# Output.net
KiCad netlist of a schematic drawn in EAGLE
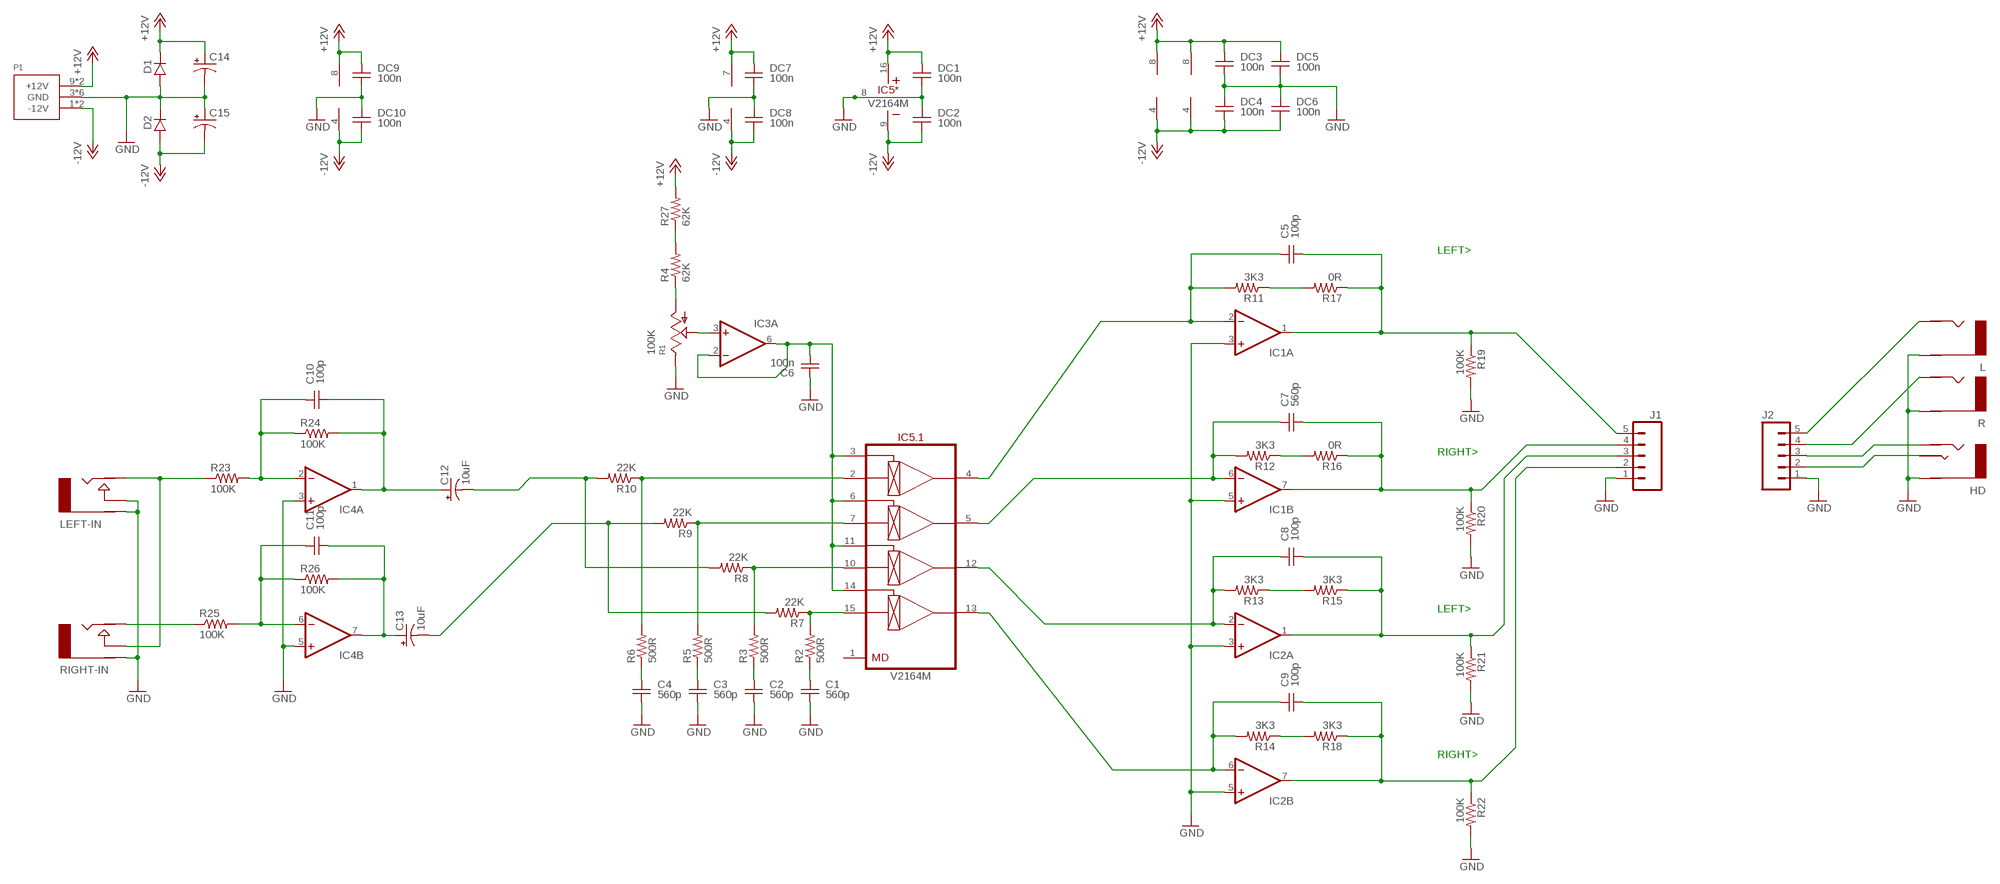
[diagram p0: schematic, sheet 1]

(export (version "E")
  (design (tool "Eeschema 10.0.6"))
  (components
    (comp (ref "C1")
      (value "560p")
      (footprint "eagle-import:C-0805")
      (libsource (lib "eagle-import") (part "CAPACITOR0805"))
    )
    (comp (ref "C2")
      (value "560p")
      (footprint "eagle-import:C-0805")
      (libsource (lib "eagle-import") (part "CAPACITOR0805"))
    )
    (comp (ref "C3")
      (value "560p")
      (footprint "eagle-import:C-0805")
      (libsource (lib "eagle-import") (part "CAPACITOR0805"))
    )
    (comp (ref "C4")
      (value "560p")
      (footprint "eagle-import:C-0805")
      (libsource (lib "eagle-import") (part "CAPACITOR0805"))
    )
    (comp (ref "C5")
      (value "100p")
      (footprint "eagle-import:C-0805")
      (libsource (lib "eagle-import") (part "CAPACITOR0805"))
    )
    (comp (ref "C6")
      (value "100n")
      (footprint "eagle-import:C-0805")
      (libsource (lib "eagle-import") (part "CAPACITOR0805"))
    )
    (comp (ref "C7")
      (value "560p")
      (footprint "eagle-import:C-0805")
      (libsource (lib "eagle-import") (part "CAPACITOR0805"))
    )
    (comp (ref "C8")
      (value "100p")
      (footprint "eagle-import:C-0805")
      (libsource (lib "eagle-import") (part "CAPACITOR0805"))
    )
    (comp (ref "C9")
      (value "100p")
      (footprint "eagle-import:C-0805")
      (libsource (lib "eagle-import") (part "CAPACITOR0805"))
    )
    (comp (ref "C10")
      (value "100p")
      (footprint "eagle-import:C-0805")
      (libsource (lib "eagle-import") (part "CAPACITOR0805"))
    )
    (comp (ref "C11")
      (value "100p")
      (footprint "eagle-import:C-0805")
      (libsource (lib "eagle-import") (part "CAPACITOR0805"))
    )
    (comp (ref "C12")
      (value "10uF")
      (footprint "eagle-import:PANASONIC_C")
      (libsource (lib "eagle-import") (part "SparkFun-Passives_CAP_POLC"))
    )
    (comp (ref "C13")
      (value "10uF")
      (footprint "eagle-import:PANASONIC_C")
      (libsource (lib "eagle-import") (part "SparkFun-Passives_CAP_POLC"))
    )
    (comp (ref "C14")
      (value "CAP_POLPTH2")
      (footprint "eagle-import:CPOL-RADIAL-10UF-25V")
      (libsource (lib "eagle-import") (part "CAP_POLPTH2"))
    )
    (comp (ref "C15")
      (value "CAP_POLPTH2")
      (footprint "eagle-import:CPOL-RADIAL-10UF-25V")
      (libsource (lib "eagle-import") (part "CAP_POLPTH2"))
    )
    (comp (ref "D1")
      (value "DIODESMA")
      (footprint "eagle-import:SMA")
      (libsource (lib "eagle-import") (part "DIODESMA"))
    )
    (comp (ref "D2")
      (value "DIODESMA")
      (footprint "eagle-import:SMA")
      (libsource (lib "eagle-import") (part "DIODESMA"))
    )
    (comp (ref "DC1")
      (value "100n")
      (footprint "eagle-import:C-0805")
      (libsource (lib "eagle-import") (part "CAPACITOR0805"))
    )
    (comp (ref "DC2")
      (value "100n")
      (footprint "eagle-import:C-0805")
      (libsource (lib "eagle-import") (part "CAPACITOR0805"))
    )
    (comp (ref "DC3")
      (value "100n")
      (footprint "eagle-import:C-0805")
      (libsource (lib "eagle-import") (part "CAPACITOR0805"))
    )
    (comp (ref "DC4")
      (value "100n")
      (footprint "eagle-import:C-0805")
      (libsource (lib "eagle-import") (part "CAPACITOR0805"))
    )
    (comp (ref "DC5")
      (value "100n")
      (footprint "eagle-import:C-0805")
      (libsource (lib "eagle-import") (part "CAPACITOR0805"))
    )
    (comp (ref "DC6")
      (value "100n")
      (footprint "eagle-import:C-0805")
      (libsource (lib "eagle-import") (part "CAPACITOR0805"))
    )
    (comp (ref "DC7")
      (value "100n")
      (footprint "eagle-import:C-0805")
      (libsource (lib "eagle-import") (part "CAPACITOR0805"))
    )
    (comp (ref "DC8")
      (value "100n")
      (footprint "eagle-import:C-0805")
      (libsource (lib "eagle-import") (part "CAPACITOR0805"))
    )
    (comp (ref "DC9")
      (value "100n")
      (footprint "eagle-import:C-0805")
      (libsource (lib "eagle-import") (part "CAPACITOR0805"))
    )
    (comp (ref "DC10")
      (value "100n")
      (footprint "eagle-import:C-0805")
      (libsource (lib "eagle-import") (part "CAPACITOR0805"))
    )
    (comp (ref "HD")
      (value "AUDIO-JACK_STEREO")
      (footprint "eagle-import:NJ3FD")
      (libsource (lib "eagle-import") (part "AUDIO-JACK_STEREO"))
    )
    (comp (ref "IC1")
      (value "OPAMP-DUAL")
      (footprint "eagle-import:SO08")
      (libsource (lib "eagle-import") (part "OPAMP-DUAL"))
    )
    (comp (ref "IC2")
      (value "OPAMP-DUAL")
      (footprint "eagle-import:SO08")
      (libsource (lib "eagle-import") (part "OPAMP-DUAL"))
    )
    (comp (ref "IC3")
      (value "OPAMP-SINGLE")
      (footprint "eagle-import:SO08")
      (libsource (lib "eagle-import") (part "OPAMP-SINGLE"))
    )
    (comp (ref "IC4")
      (value "OPAMP-DUAL")
      (footprint "eagle-import:SO08")
      (libsource (lib "eagle-import") (part "OPAMP-DUAL"))
    )
    (comp (ref "IC5")
      (value "V2164M")
      (footprint "eagle-import:SO-16")
      (libsource (lib "eagle-import") (part "V2164M"))
    )
    (comp (ref "J1")
      (value "CONN2")
      (footprint "eagle-import:1X05_LOCK")
      (libsource (lib "eagle-import") (part "M05LOCK"))
    )
    (comp (ref "J2")
      (value "CONN")
      (footprint "eagle-import:1X05_LOCK")
      (libsource (lib "eagle-import") (part "M05LOCK"))
    )
    (comp (ref "L")
      (value "AUDIO-JACK-MONO")
      (footprint "eagle-import:NJ2FD")
      (libsource (lib "eagle-import") (part "AUDIO-JACK-MONO"))
    )
    (comp (ref "LEFT-IN")
      (value "AUDIO-JACKINLINE")
      (footprint "eagle-import:ERTHENVAR-JACK-INLINE")
      (libsource (lib "eagle-import") (part "AUDIO-JACKINLINE"))
    )
    (comp (ref "P1")
      (value "POWER_SIMPLE10_SHROUDED")
      (footprint "eagle-import:POWER_10_SHROUDED")
      (libsource (lib "eagle-import") (part "POWER_SIMPLE10_SHROUDED"))
    )
    (comp (ref "R")
      (value "AUDIO-JACK-MONO")
      (footprint "eagle-import:NJ2FD")
      (libsource (lib "eagle-import") (part "AUDIO-JACK-MONO"))
    )
    (comp (ref "R1")
      (value "100K")
      (footprint "eagle-import:POT-ALPHA-9MM")
      (libsource (lib "eagle-import") (part "POTALPHA-9MM"))
    )
    (comp (ref "R2")
      (value "500R")
      (footprint "eagle-import:R-0805-MILL")
      (libsource (lib "eagle-import") (part "RESISTOR0805"))
    )
    (comp (ref "R3")
      (value "500R")
      (footprint "eagle-import:R-0805-MILL")
      (libsource (lib "eagle-import") (part "RESISTOR0805"))
    )
    (comp (ref "R4")
      (value "62K")
      (footprint "eagle-import:R-0805-MILL")
      (libsource (lib "eagle-import") (part "RESISTOR0805"))
    )
    (comp (ref "R5")
      (value "500R")
      (footprint "eagle-import:R-0805-MILL")
      (libsource (lib "eagle-import") (part "RESISTOR0805"))
    )
    (comp (ref "R6")
      (value "500R")
      (footprint "eagle-import:R-0805-MILL")
      (libsource (lib "eagle-import") (part "RESISTOR0805"))
    )
    (comp (ref "R7")
      (value "22K")
      (footprint "eagle-import:R-0805-MILL")
      (libsource (lib "eagle-import") (part "RESISTOR0805"))
    )
    (comp (ref "R8")
      (value "22K")
      (footprint "eagle-import:R-0805-MILL")
      (libsource (lib "eagle-import") (part "RESISTOR0805"))
    )
    (comp (ref "R9")
      (value "22K")
      (footprint "eagle-import:R-0805-MILL")
      (libsource (lib "eagle-import") (part "RESISTOR0805"))
    )
    (comp (ref "R10")
      (value "22K")
      (footprint "eagle-import:R-0805-MILL")
      (libsource (lib "eagle-import") (part "RESISTOR0805"))
    )
    (comp (ref "R11")
      (value "3K3")
      (footprint "eagle-import:R-0805-MILL")
      (libsource (lib "eagle-import") (part "RESISTOR0805"))
    )
    (comp (ref "R12")
      (value "3K3")
      (footprint "eagle-import:R-0805-MILL")
      (libsource (lib "eagle-import") (part "RESISTOR0805"))
    )
    (comp (ref "R13")
      (value "3K3")
      (footprint "eagle-import:R-0805-MILL")
      (libsource (lib "eagle-import") (part "RESISTOR0805"))
    )
    (comp (ref "R14")
      (value "3K3")
      (footprint "eagle-import:R-0805-MILL")
      (libsource (lib "eagle-import") (part "RESISTOR0805"))
    )
    (comp (ref "R15")
      (value "3K3")
      (footprint "eagle-import:R-0805-MILL")
      (libsource (lib "eagle-import") (part "RESISTOR0805"))
    )
    (comp (ref "R16")
      (value "0R")
      (footprint "eagle-import:R-0805-MILL")
      (libsource (lib "eagle-import") (part "RESISTOR0805"))
    )
    (comp (ref "R17")
      (value "0R")
      (footprint "eagle-import:R-0805-MILL")
      (libsource (lib "eagle-import") (part "RESISTOR0805"))
    )
    (comp (ref "R18")
      (value "3K3")
      (footprint "eagle-import:R-0805-MILL")
      (libsource (lib "eagle-import") (part "RESISTOR0805"))
    )
    (comp (ref "R19")
      (value "100K")
      (footprint "eagle-import:R-0805-MILL")
      (libsource (lib "eagle-import") (part "RESISTOR0805"))
    )
    (comp (ref "R20")
      (value "100K")
      (footprint "eagle-import:R-0805-MILL")
      (libsource (lib "eagle-import") (part "RESISTOR0805"))
    )
    (comp (ref "R21")
      (value "100K")
      (footprint "eagle-import:R-0805-MILL")
      (libsource (lib "eagle-import") (part "RESISTOR0805"))
    )
    (comp (ref "R22")
      (value "100K")
      (footprint "eagle-import:R-0805-MILL")
      (libsource (lib "eagle-import") (part "RESISTOR0805"))
    )
    (comp (ref "R23")
      (value "100K")
      (footprint "eagle-import:R-0805-MILL")
      (libsource (lib "eagle-import") (part "RESISTOR0805"))
    )
    (comp (ref "R24")
      (value "100K")
      (footprint "eagle-import:R-0805-MILL")
      (libsource (lib "eagle-import") (part "RESISTOR0805"))
    )
    (comp (ref "R25")
      (value "100K")
      (footprint "eagle-import:R-0805-MILL")
      (libsource (lib "eagle-import") (part "RESISTOR0805"))
    )
    (comp (ref "R26")
      (value "100K")
      (footprint "eagle-import:R-0805-MILL")
      (libsource (lib "eagle-import") (part "RESISTOR0805"))
    )
    (comp (ref "R27")
      (value "62K")
      (footprint "eagle-import:R-0805-MILL")
      (libsource (lib "eagle-import") (part "RESISTOR0805"))
    )
    (comp (ref "RIGHT-IN")
      (value "AUDIO-JACKINLINE")
      (footprint "eagle-import:ERTHENVAR-JACK-INLINE")
      (libsource (lib "eagle-import") (part "AUDIO-JACKINLINE"))
    )
  )
  (nets
    (net (code "1") (name "+12V") (class "Default")
      (node (ref "C14") (pin "1") (pinfunction "+_1") (pintype "passive"))
      (node (ref "D1") (pin "K") (pinfunction "C_K") (pintype "passive"))
      (node (ref "DC1") (pin "1") (pinfunction "1_1") (pintype "passive"))
      (node (ref "DC3") (pin "1") (pinfunction "1_1") (pintype "passive"))
      (node (ref "DC5") (pin "1") (pinfunction "1_1") (pintype "passive"))
      (node (ref "DC7") (pin "1") (pinfunction "1_1") (pintype "passive"))
      (node (ref "DC9") (pin "1") (pinfunction "1_1") (pintype "passive"))
      (node (ref "IC1") (pin "8") (pinfunction "V+_8") (pintype "power_in"))
      (node (ref "IC2") (pin "8") (pinfunction "V+_8") (pintype "power_in"))
      (node (ref "IC3") (pin "7") (pinfunction "V+_7") (pintype "power_in"))
      (node (ref "IC4") (pin "8") (pinfunction "V+_8") (pintype "power_in"))
      (node (ref "IC5") (pin "16") (pinfunction "V+_16") (pintype "power_in"))
      (node (ref "P1") (pin "10") (pinfunction "+12V_10") (pintype "bidirectional"))
      (node (ref "P1") (pin "9") (pinfunction "+12V_9") (pintype "bidirectional"))
      (node (ref "R27") (pin "P$2") (pinfunction "2_P$2") (pintype "passive"))
    )
    (net (code "2") (name "-12V") (class "Default")
      (node (ref "C15") (pin "2") (pinfunction "-_2") (pintype "passive"))
      (node (ref "D2") (pin "A") (pinfunction "A_A") (pintype "passive"))
      (node (ref "DC10") (pin "2") (pinfunction "2_2") (pintype "passive"))
      (node (ref "DC2") (pin "2") (pinfunction "2_2") (pintype "passive"))
      (node (ref "DC4") (pin "2") (pinfunction "2_2") (pintype "passive"))
      (node (ref "DC6") (pin "2") (pinfunction "2_2") (pintype "passive"))
      (node (ref "DC8") (pin "2") (pinfunction "2_2") (pintype "passive"))
      (node (ref "IC1") (pin "4") (pinfunction "V-_4") (pintype "power_in"))
      (node (ref "IC2") (pin "4") (pinfunction "V-_4") (pintype "power_in"))
      (node (ref "IC3") (pin "4") (pinfunction "V-_4") (pintype "power_in"))
      (node (ref "IC4") (pin "4") (pinfunction "V-_4") (pintype "power_in"))
      (node (ref "IC5") (pin "9") (pinfunction "V-_9") (pintype "power_in"))
      (node (ref "P1") (pin "1") (pinfunction "-12V_1") (pintype "bidirectional"))
      (node (ref "P1") (pin "2") (pinfunction "-12V_2") (pintype "bidirectional"))
    )
    (net (code "3") (name "GND") (class "Default")
      (node (ref "C1") (pin "2") (pinfunction "2_2") (pintype "passive"))
      (node (ref "C14") (pin "2") (pinfunction "-_2") (pintype "passive"))
      (node (ref "C15") (pin "1") (pinfunction "+_1") (pintype "passive"))
      (node (ref "C2") (pin "2") (pinfunction "2_2") (pintype "passive"))
      (node (ref "C3") (pin "2") (pinfunction "2_2") (pintype "passive"))
      (node (ref "C4") (pin "2") (pinfunction "2_2") (pintype "passive"))
      (node (ref "C6") (pin "1") (pinfunction "1_1") (pintype "passive"))
      (node (ref "D1") (pin "A") (pinfunction "A_A") (pintype "passive"))
      (node (ref "D2") (pin "K") (pinfunction "C_K") (pintype "passive"))
      (node (ref "DC1") (pin "2") (pinfunction "2_2") (pintype "passive"))
      (node (ref "DC10") (pin "1") (pinfunction "1_1") (pintype "passive"))
      (node (ref "DC2") (pin "1") (pinfunction "1_1") (pintype "passive"))
      (node (ref "DC3") (pin "2") (pinfunction "2_2") (pintype "passive"))
      (node (ref "DC4") (pin "1") (pinfunction "1_1") (pintype "passive"))
      (node (ref "DC5") (pin "2") (pinfunction "2_2") (pintype "passive"))
      (node (ref "DC6") (pin "1") (pinfunction "1_1") (pintype "passive"))
      (node (ref "DC7") (pin "2") (pinfunction "2_2") (pintype "passive"))
      (node (ref "DC8") (pin "1") (pinfunction "1_1") (pintype "passive"))
      (node (ref "DC9") (pin "2") (pinfunction "2_2") (pintype "passive"))
      (node (ref "HD") (pin "R") (pinfunction "RING_R") (pintype "bidirectional"))
      (node (ref "IC1") (pin "3") (pinfunction "+IN_3") (pintype "input"))
      (node (ref "IC1") (pin "5") (pinfunction "+IN_5") (pintype "input"))
      (node (ref "IC2") (pin "3") (pinfunction "+IN_3") (pintype "input"))
      (node (ref "IC2") (pin "5") (pinfunction "+IN_5") (pintype "input"))
      (node (ref "IC4") (pin "3") (pinfunction "+IN_3") (pintype "input"))
      (node (ref "IC4") (pin "5") (pinfunction "+IN_5") (pintype "input"))
      (node (ref "IC5") (pin "8") (pinfunction "GND_8") (pintype "power_in"))
      (node (ref "J1") (pin "1") (pinfunction "1_1") (pintype "passive"))
      (node (ref "J2") (pin "1") (pinfunction "1_1") (pintype "passive"))
      (node (ref "L") (pin "S") (pinfunction "RING_S") (pintype "bidirectional"))
      (node (ref "LEFT-IN") (pin "G") (pinfunction "RING_G") (pintype "bidirectional"))
      (node (ref "LEFT-IN") (pin "N") (pinfunction "NORM_N") (pintype "bidirectional"))
      (node (ref "P1") (pin "3") (pinfunction "GND_3") (pintype "bidirectional"))
      (node (ref "P1") (pin "4") (pinfunction "GND_4") (pintype "bidirectional"))
      (node (ref "P1") (pin "5") (pinfunction "GND_5") (pintype "bidirectional"))
      (node (ref "P1") (pin "6") (pinfunction "GND_6") (pintype "bidirectional"))
      (node (ref "P1") (pin "7") (pinfunction "GND_7") (pintype "bidirectional"))
      (node (ref "P1") (pin "8") (pinfunction "GND_8") (pintype "bidirectional"))
      (node (ref "R") (pin "S") (pinfunction "RING_S") (pintype "bidirectional"))
      (node (ref "R1") (pin "B") (pinfunction "E_B") (pintype "passive"))
      (node (ref "R19") (pin "P$2") (pinfunction "2_P$2") (pintype "passive"))
      (node (ref "R20") (pin "P$2") (pinfunction "2_P$2") (pintype "passive"))
      (node (ref "R21") (pin "P$2") (pinfunction "2_P$2") (pintype "passive"))
      (node (ref "R22") (pin "P$2") (pinfunction "2_P$2") (pintype "passive"))
      (node (ref "RIGHT-IN") (pin "G") (pinfunction "RING_G") (pintype "bidirectional"))
    )
    (net (code "4") (name "Net-(HD-SLEEVE)") (class "Default")
      (node (ref "HD") (pin "S") (pinfunction "SLEEVE_S") (pintype "bidirectional"))
      (node (ref "J2") (pin "2") (pinfunction "2_2") (pintype "passive"))
    )
    (net (code "5") (name "Net-(HD-TIP)") (class "Default")
      (node (ref "HD") (pin "T") (pinfunction "TIP_T") (pintype "bidirectional"))
      (node (ref "J2") (pin "3") (pinfunction "3_3") (pintype "passive"))
    )
    (net (code "6") (name "Net-(IC1A--IN)") (class "Default")
      (node (ref "C5") (pin "1") (pinfunction "1_1") (pintype "passive"))
      (node (ref "IC1") (pin "2") (pinfunction "-IN_2") (pintype "input"))
      (node (ref "IC5") (pin "4") (pinfunction "OUT1_4") (pintype "output"))
      (node (ref "R11") (pin "P$2") (pinfunction "2_P$2") (pintype "passive"))
    )
    (net (code "7") (name "Net-(IC1A-OUT)") (class "Default")
      (node (ref "C5") (pin "2") (pinfunction "2_2") (pintype "passive"))
      (node (ref "IC1") (pin "1") (pinfunction "OUT_1") (pintype "output"))
      (node (ref "J1") (pin "5") (pinfunction "5_5") (pintype "passive"))
      (node (ref "R17") (pin "P$1") (pinfunction "1_P$1") (pintype "passive"))
      (node (ref "R19") (pin "P$1") (pinfunction "1_P$1") (pintype "passive"))
    )
    (net (code "8") (name "Net-(IC1B--IN)") (class "Default")
      (node (ref "C7") (pin "1") (pinfunction "1_1") (pintype "passive"))
      (node (ref "IC1") (pin "6") (pinfunction "-IN_6") (pintype "input"))
      (node (ref "IC5") (pin "5") (pinfunction "OUT2_5") (pintype "output"))
      (node (ref "R12") (pin "P$2") (pinfunction "2_P$2") (pintype "passive"))
    )
    (net (code "9") (name "Net-(IC1B-OUT)") (class "Default")
      (node (ref "C7") (pin "2") (pinfunction "2_2") (pintype "passive"))
      (node (ref "IC1") (pin "7") (pinfunction "OUT_7") (pintype "output"))
      (node (ref "J1") (pin "4") (pinfunction "4_4") (pintype "passive"))
      (node (ref "R16") (pin "P$1") (pinfunction "1_P$1") (pintype "passive"))
      (node (ref "R20") (pin "P$1") (pinfunction "1_P$1") (pintype "passive"))
    )
    (net (code "10") (name "Net-(IC2A--IN)") (class "Default")
      (node (ref "C8") (pin "1") (pinfunction "1_1") (pintype "passive"))
      (node (ref "IC2") (pin "2") (pinfunction "-IN_2") (pintype "input"))
      (node (ref "IC5") (pin "12") (pinfunction "OUT3_12") (pintype "output"))
      (node (ref "R13") (pin "P$2") (pinfunction "2_P$2") (pintype "passive"))
    )
    (net (code "11") (name "Net-(IC2A-OUT)") (class "Default")
      (node (ref "C8") (pin "2") (pinfunction "2_2") (pintype "passive"))
      (node (ref "IC2") (pin "1") (pinfunction "OUT_1") (pintype "output"))
      (node (ref "J1") (pin "3") (pinfunction "3_3") (pintype "passive"))
      (node (ref "R15") (pin "P$1") (pinfunction "1_P$1") (pintype "passive"))
      (node (ref "R21") (pin "P$1") (pinfunction "1_P$1") (pintype "passive"))
    )
    (net (code "12") (name "Net-(IC2B--IN)") (class "Default")
      (node (ref "C9") (pin "1") (pinfunction "1_1") (pintype "passive"))
      (node (ref "IC2") (pin "6") (pinfunction "-IN_6") (pintype "input"))
      (node (ref "IC5") (pin "13") (pinfunction "OUT4_13") (pintype "output"))
      (node (ref "R14") (pin "P$2") (pinfunction "2_P$2") (pintype "passive"))
    )
    (net (code "13") (name "Net-(IC2B-OUT)") (class "Default")
      (node (ref "C9") (pin "2") (pinfunction "2_2") (pintype "passive"))
      (node (ref "IC2") (pin "7") (pinfunction "OUT_7") (pintype "output"))
      (node (ref "J1") (pin "2") (pinfunction "2_2") (pintype "passive"))
      (node (ref "R18") (pin "P$1") (pinfunction "1_P$1") (pintype "passive"))
      (node (ref "R22") (pin "P$1") (pinfunction "1_P$1") (pintype "passive"))
    )
    (net (code "14") (name "Net-(IC3A-+IN)") (class "Default")
      (node (ref "IC3") (pin "3") (pinfunction "+IN_3") (pintype "input"))
      (node (ref "R1") (pin "W") (pinfunction "S_W") (pintype "passive"))
    )
    (net (code "15") (name "Net-(IC3A--IN)") (class "Default")
      (node (ref "C6") (pin "2") (pinfunction "2_2") (pintype "passive"))
      (node (ref "IC3") (pin "2") (pinfunction "-IN_2") (pintype "input"))
      (node (ref "IC3") (pin "6") (pinfunction "OUT_6") (pintype "output"))
      (node (ref "IC5") (pin "11") (pinfunction "CV3_11") (pintype "input"))
      (node (ref "IC5") (pin "14") (pinfunction "CV4_14") (pintype "input"))
      (node (ref "IC5") (pin "3") (pinfunction "CV1_3") (pintype "input"))
      (node (ref "IC5") (pin "6") (pinfunction "CV2_6") (pintype "input"))
    )
    (net (code "16") (name "Net-(IC4A--IN)") (class "Default")
      (node (ref "C10") (pin "1") (pinfunction "1_1") (pintype "passive"))
      (node (ref "IC4") (pin "2") (pinfunction "-IN_2") (pintype "input"))
      (node (ref "R23") (pin "P$2") (pinfunction "2_P$2") (pintype "passive"))
      (node (ref "R24") (pin "P$1") (pinfunction "1_P$1") (pintype "passive"))
    )
    (net (code "17") (name "Net-(IC4A-OUT)") (class "Default")
      (node (ref "C10") (pin "2") (pinfunction "2_2") (pintype "passive"))
      (node (ref "C12") (pin "+") (pinfunction "+_+") (pintype "passive"))
      (node (ref "IC4") (pin "1") (pinfunction "OUT_1") (pintype "output"))
      (node (ref "R24") (pin "P$2") (pinfunction "2_P$2") (pintype "passive"))
    )
    (net (code "18") (name "Net-(IC4B--IN)") (class "Default")
      (node (ref "C11") (pin "1") (pinfunction "1_1") (pintype "passive"))
      (node (ref "IC4") (pin "6") (pinfunction "-IN_6") (pintype "input"))
      (node (ref "R25") (pin "P$2") (pinfunction "2_P$2") (pintype "passive"))
      (node (ref "R26") (pin "P$1") (pinfunction "1_P$1") (pintype "passive"))
    )
    (net (code "19") (name "Net-(IC4B-OUT)") (class "Default")
      (node (ref "C11") (pin "2") (pinfunction "2_2") (pintype "passive"))
      (node (ref "C13") (pin "+") (pinfunction "+_+") (pintype "passive"))
      (node (ref "IC4") (pin "7") (pinfunction "OUT_7") (pintype "output"))
      (node (ref "R26") (pin "P$2") (pinfunction "2_P$2") (pintype "passive"))
    )
    (net (code "20") (name "Net-(IC5B-IN1)") (class "Default")
      (node (ref "IC5") (pin "2") (pinfunction "IN1_2") (pintype "input"))
      (node (ref "R10") (pin "P$1") (pinfunction "1_P$1") (pintype "passive"))
      (node (ref "R6") (pin "P$2") (pinfunction "2_P$2") (pintype "passive"))
    )
    (net (code "21") (name "Net-(IC5B-IN2)") (class "Default")
      (node (ref "IC5") (pin "7") (pinfunction "IN2_7") (pintype "input"))
      (node (ref "R5") (pin "P$2") (pinfunction "2_P$2") (pintype "passive"))
      (node (ref "R9") (pin "P$1") (pinfunction "1_P$1") (pintype "passive"))
    )
    (net (code "22") (name "Net-(IC5B-IN3)") (class "Default")
      (node (ref "IC5") (pin "10") (pinfunction "IN3_10") (pintype "input"))
      (node (ref "R3") (pin "P$2") (pinfunction "2_P$2") (pintype "passive"))
      (node (ref "R8") (pin "P$1") (pinfunction "1_P$1") (pintype "passive"))
    )
    (net (code "23") (name "Net-(IC5B-IN4)") (class "Default")
      (node (ref "IC5") (pin "15") (pinfunction "IN4_15") (pintype "input"))
      (node (ref "R2") (pin "P$2") (pinfunction "2_P$2") (pintype "passive"))
      (node (ref "R7") (pin "P$1") (pinfunction "1_P$1") (pintype "passive"))
    )
    (net (code "24") (name "Net-(L-TIP)") (class "Default")
      (node (ref "J2") (pin "5") (pinfunction "5_5") (pintype "passive"))
      (node (ref "L") (pin "T") (pinfunction "TIP_T") (pintype "bidirectional"))
    )
    (net (code "25") (name "Net-(LEFT-IN-TIP)") (class "Default")
      (node (ref "LEFT-IN") (pin "T") (pinfunction "TIP_T") (pintype "bidirectional"))
      (node (ref "R23") (pin "P$1") (pinfunction "1_P$1") (pintype "passive"))
      (node (ref "RIGHT-IN") (pin "N") (pinfunction "NORM_N") (pintype "bidirectional"))
    )
    (net (code "26") (name "Net-(R-TIP)") (class "Default")
      (node (ref "J2") (pin "4") (pinfunction "4_4") (pintype "passive"))
      (node (ref "R") (pin "T") (pinfunction "TIP_T") (pintype "bidirectional"))
    )
    (net (code "27") (name "Net-(R2-1)") (class "Default")
      (node (ref "C1") (pin "1") (pinfunction "1_1") (pintype "passive"))
      (node (ref "R2") (pin "P$1") (pinfunction "1_P$1") (pintype "passive"))
    )
    (net (code "28") (name "Net-(R3-1)") (class "Default")
      (node (ref "C2") (pin "1") (pinfunction "1_1") (pintype "passive"))
      (node (ref "R3") (pin "P$1") (pinfunction "1_P$1") (pintype "passive"))
    )
    (net (code "29") (name "Net-(R4-1)") (class "Default")
      (node (ref "R1") (pin "A") (pinfunction "A_A") (pintype "passive"))
      (node (ref "R4") (pin "P$1") (pinfunction "1_P$1") (pintype "passive"))
    )
    (net (code "30") (name "Net-(R5-1)") (class "Default")
      (node (ref "C3") (pin "1") (pinfunction "1_1") (pintype "passive"))
      (node (ref "R5") (pin "P$1") (pinfunction "1_P$1") (pintype "passive"))
    )
    (net (code "31") (name "Net-(R6-1)") (class "Default")
      (node (ref "C4") (pin "1") (pinfunction "1_1") (pintype "passive"))
      (node (ref "R6") (pin "P$1") (pinfunction "1_P$1") (pintype "passive"))
    )
    (net (code "32") (name "Net-(R7-2)") (class "Default")
      (node (ref "C13") (pin "-") (pinfunction "-_-") (pintype "passive"))
      (node (ref "R7") (pin "P$2") (pinfunction "2_P$2") (pintype "passive"))
      (node (ref "R9") (pin "P$2") (pinfunction "2_P$2") (pintype "passive"))
    )
    (net (code "33") (name "Net-(R10-2)") (class "Default")
      (node (ref "C12") (pin "-") (pinfunction "-_-") (pintype "passive"))
      (node (ref "R10") (pin "P$2") (pinfunction "2_P$2") (pintype "passive"))
      (node (ref "R8") (pin "P$2") (pinfunction "2_P$2") (pintype "passive"))
    )
    (net (code "34") (name "Net-(R11-1)") (class "Default")
      (node (ref "R11") (pin "P$1") (pinfunction "1_P$1") (pintype "passive"))
      (node (ref "R17") (pin "P$2") (pinfunction "2_P$2") (pintype "passive"))
    )
    (net (code "35") (name "Net-(R12-1)") (class "Default")
      (node (ref "R12") (pin "P$1") (pinfunction "1_P$1") (pintype "passive"))
      (node (ref "R16") (pin "P$2") (pinfunction "2_P$2") (pintype "passive"))
    )
    (net (code "36") (name "Net-(R13-1)") (class "Default")
      (node (ref "R13") (pin "P$1") (pinfunction "1_P$1") (pintype "passive"))
      (node (ref "R15") (pin "P$2") (pinfunction "2_P$2") (pintype "passive"))
    )
    (net (code "37") (name "Net-(R14-1)") (class "Default")
      (node (ref "R14") (pin "P$1") (pinfunction "1_P$1") (pintype "passive"))
      (node (ref "R18") (pin "P$2") (pinfunction "2_P$2") (pintype "passive"))
    )
    (net (code "38") (name "Net-(R25-1)") (class "Default")
      (node (ref "R25") (pin "P$1") (pinfunction "1_P$1") (pintype "passive"))
      (node (ref "RIGHT-IN") (pin "T") (pinfunction "TIP_T") (pintype "bidirectional"))
    )
    (net (code "39") (name "Net-(R27-1)") (class "Default")
      (node (ref "R27") (pin "P$1") (pinfunction "1_P$1") (pintype "passive"))
      (node (ref "R4") (pin "P$2") (pinfunction "2_P$2") (pintype "passive"))
    )
    (net (code "40") (name "unconnected-(IC5B-MD-Pad1)") (class "Default")
      (node (ref "IC5") (pin "1") (pinfunction "MD_1") (pintype "output"))
    )
  )
)
